# WaveformMorpher.net
KiCad netlist of a schematic drawn in EAGLE
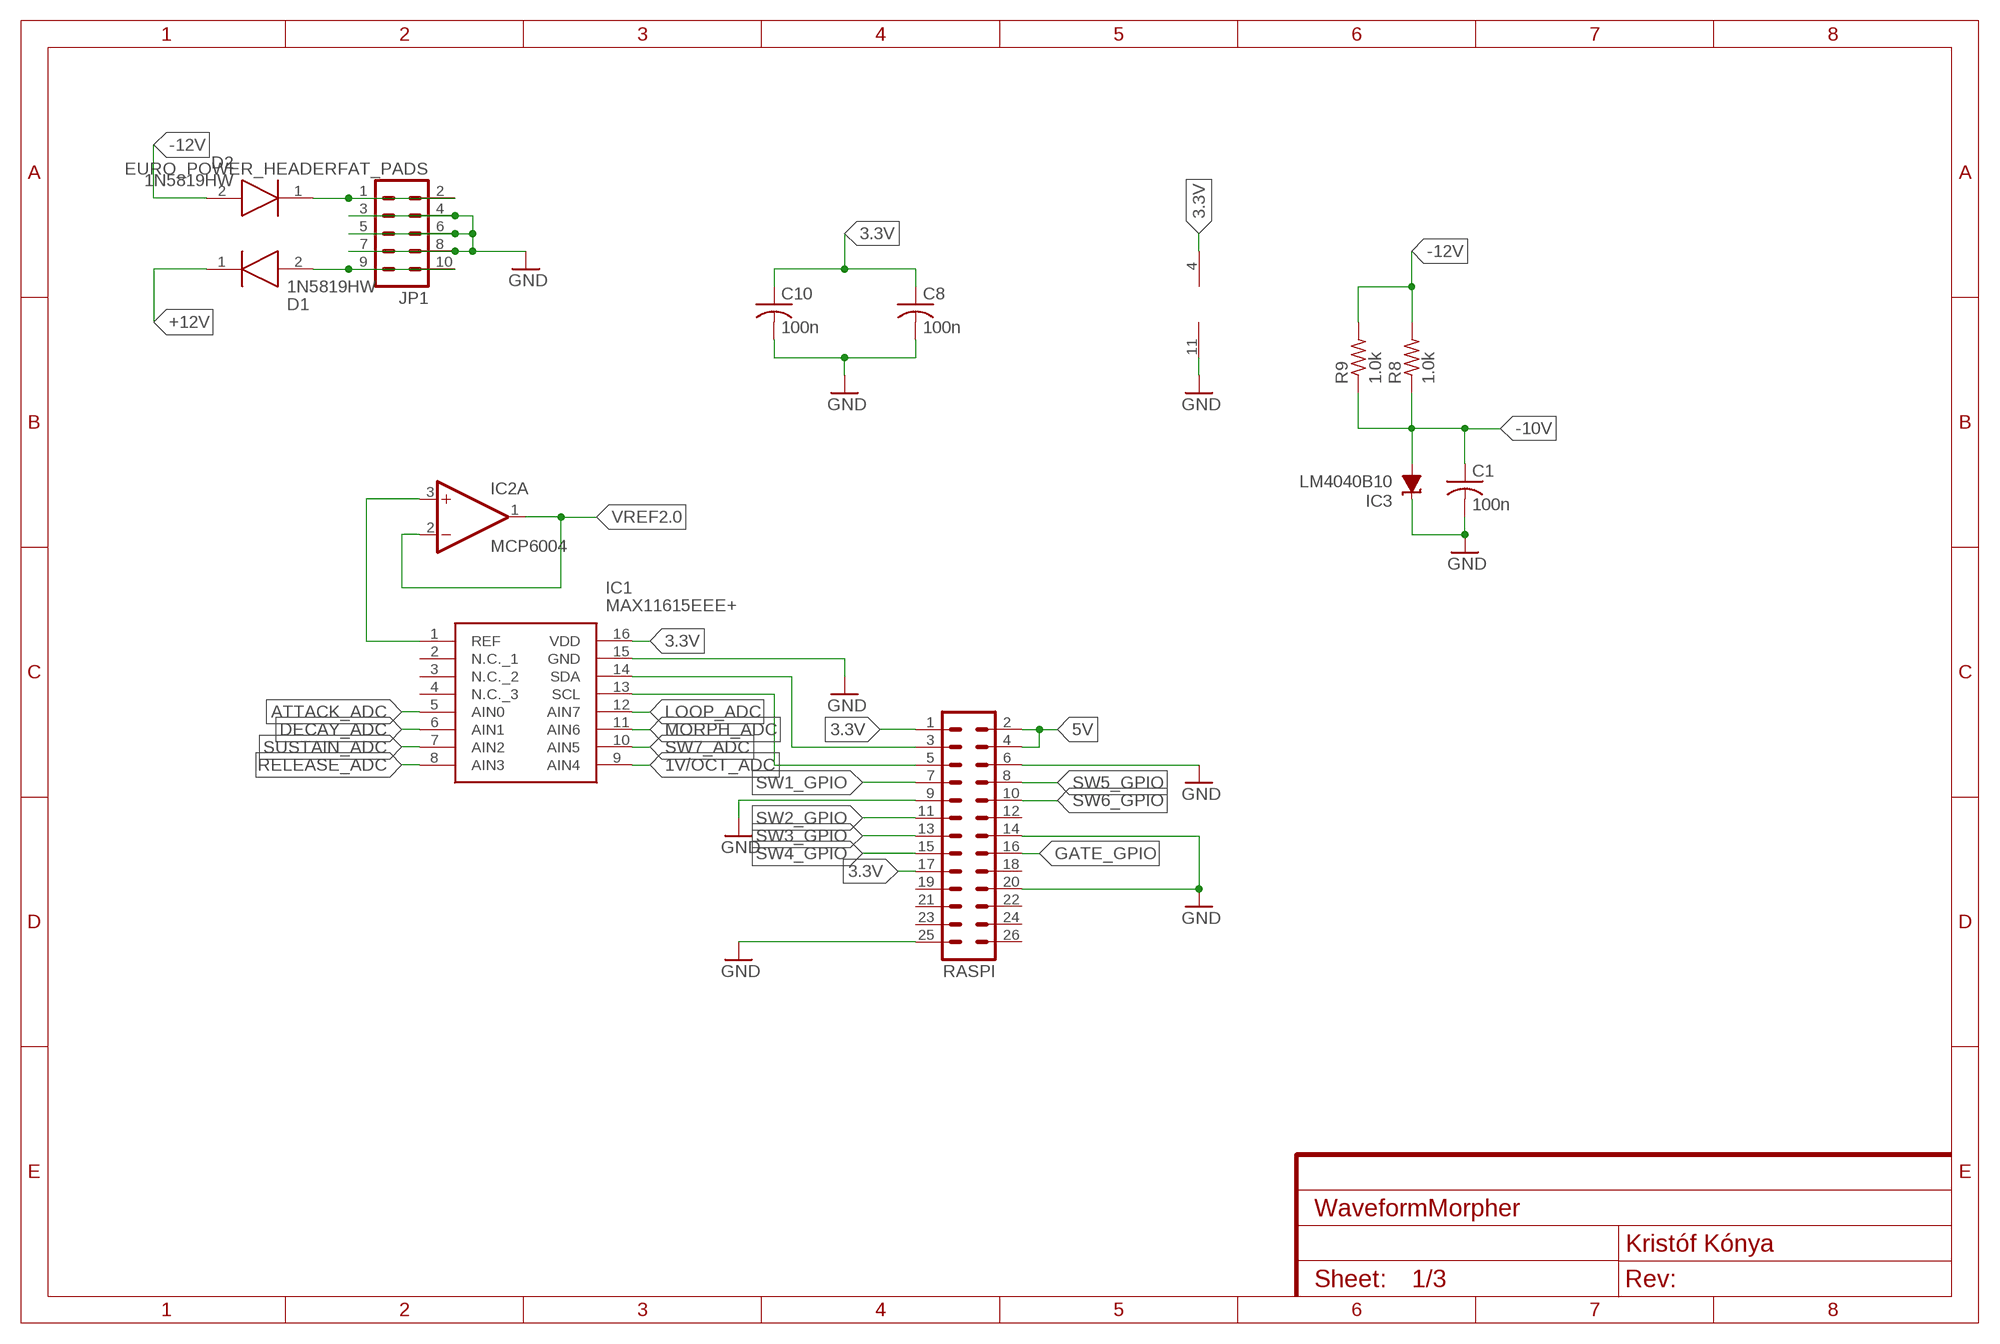
[diagram p0: schematic, sheet 1]
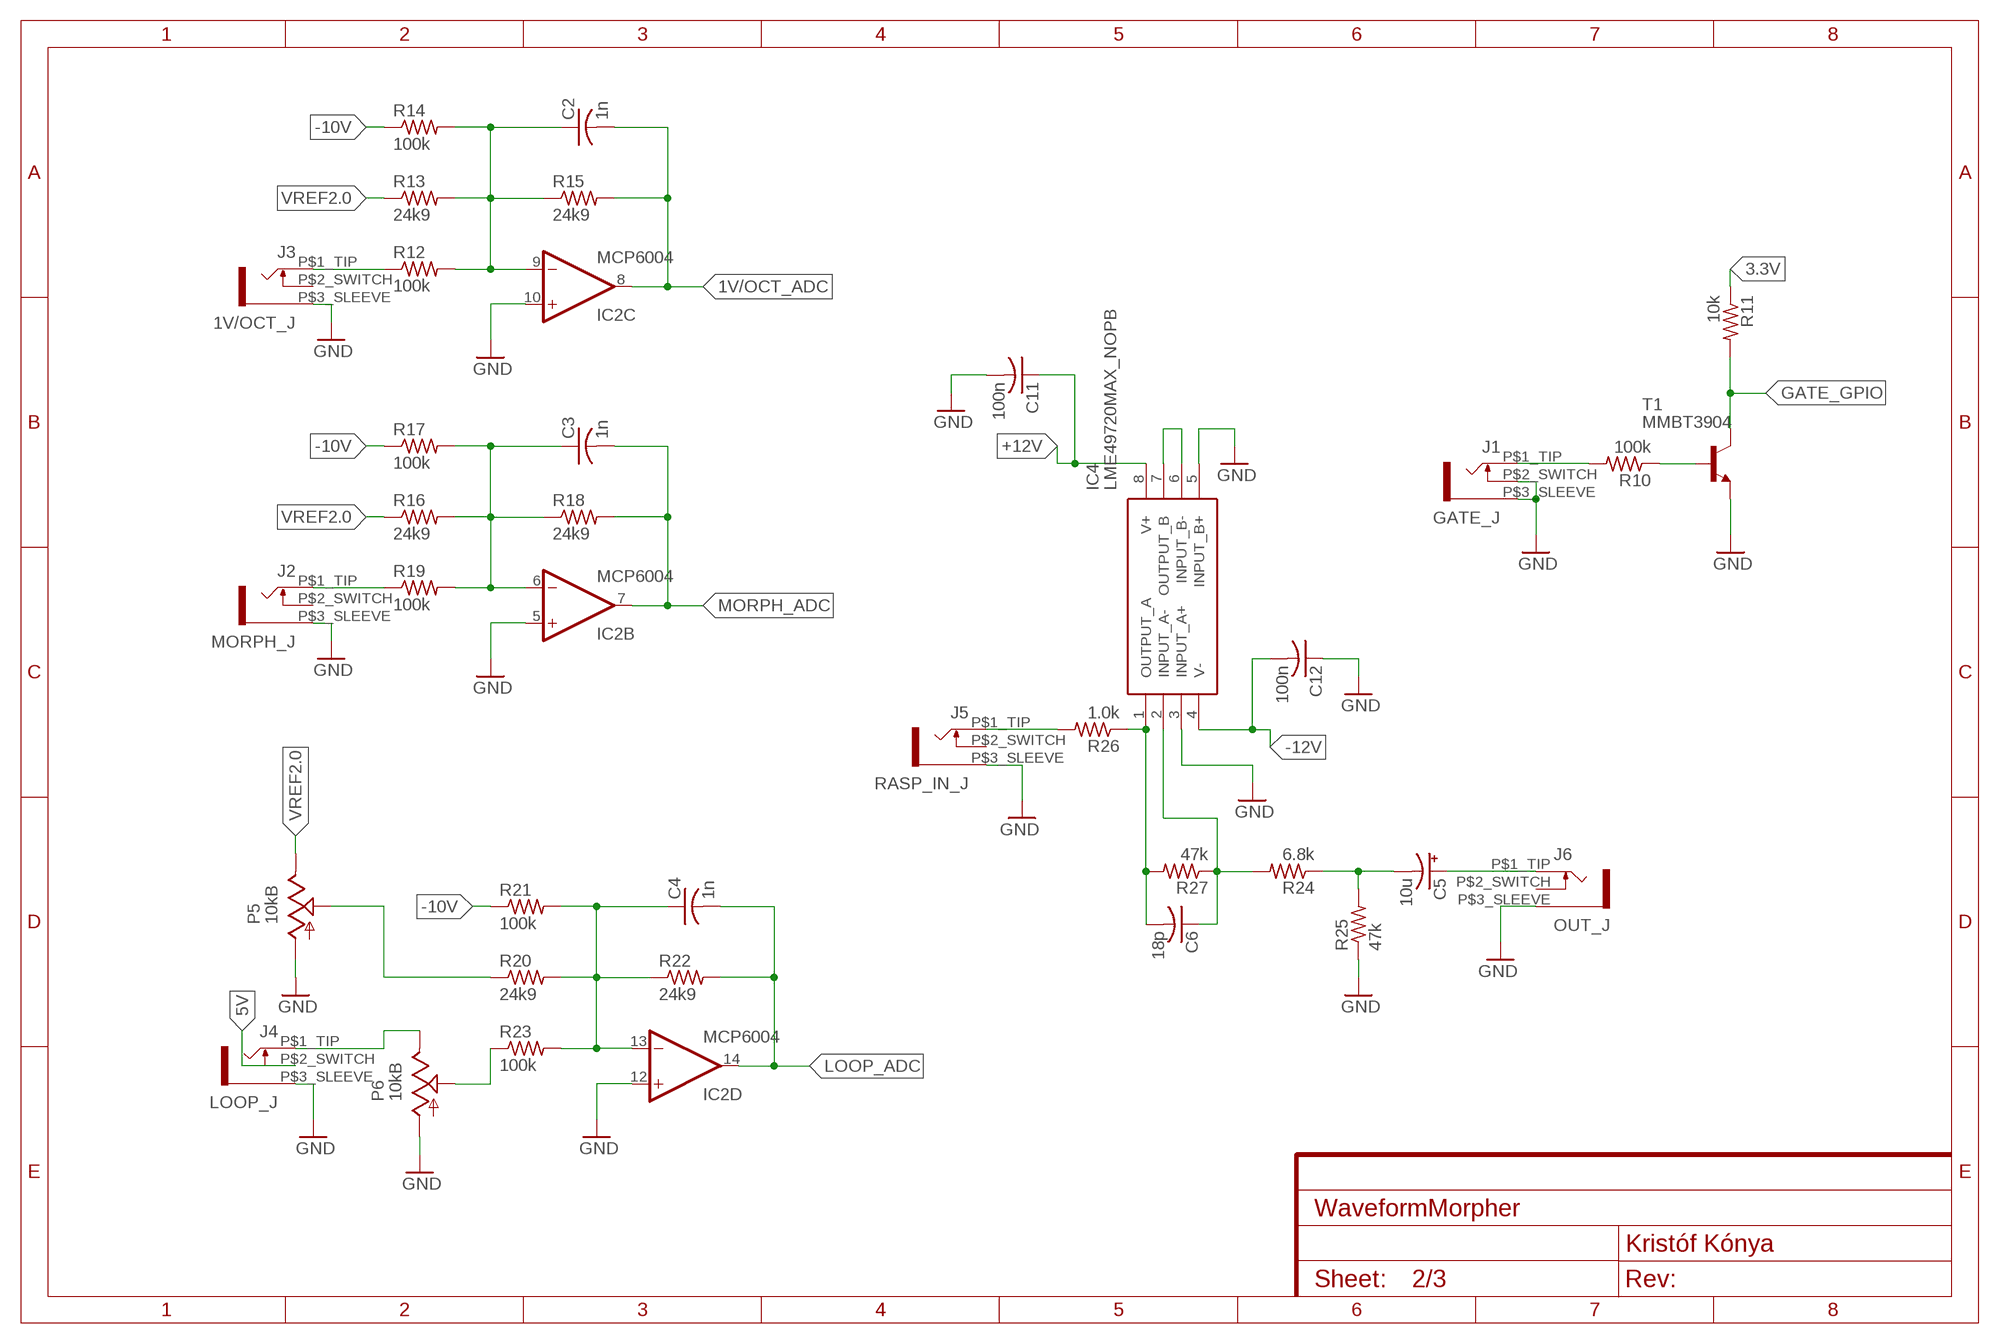
[diagram p1: schematic, sheet 2]
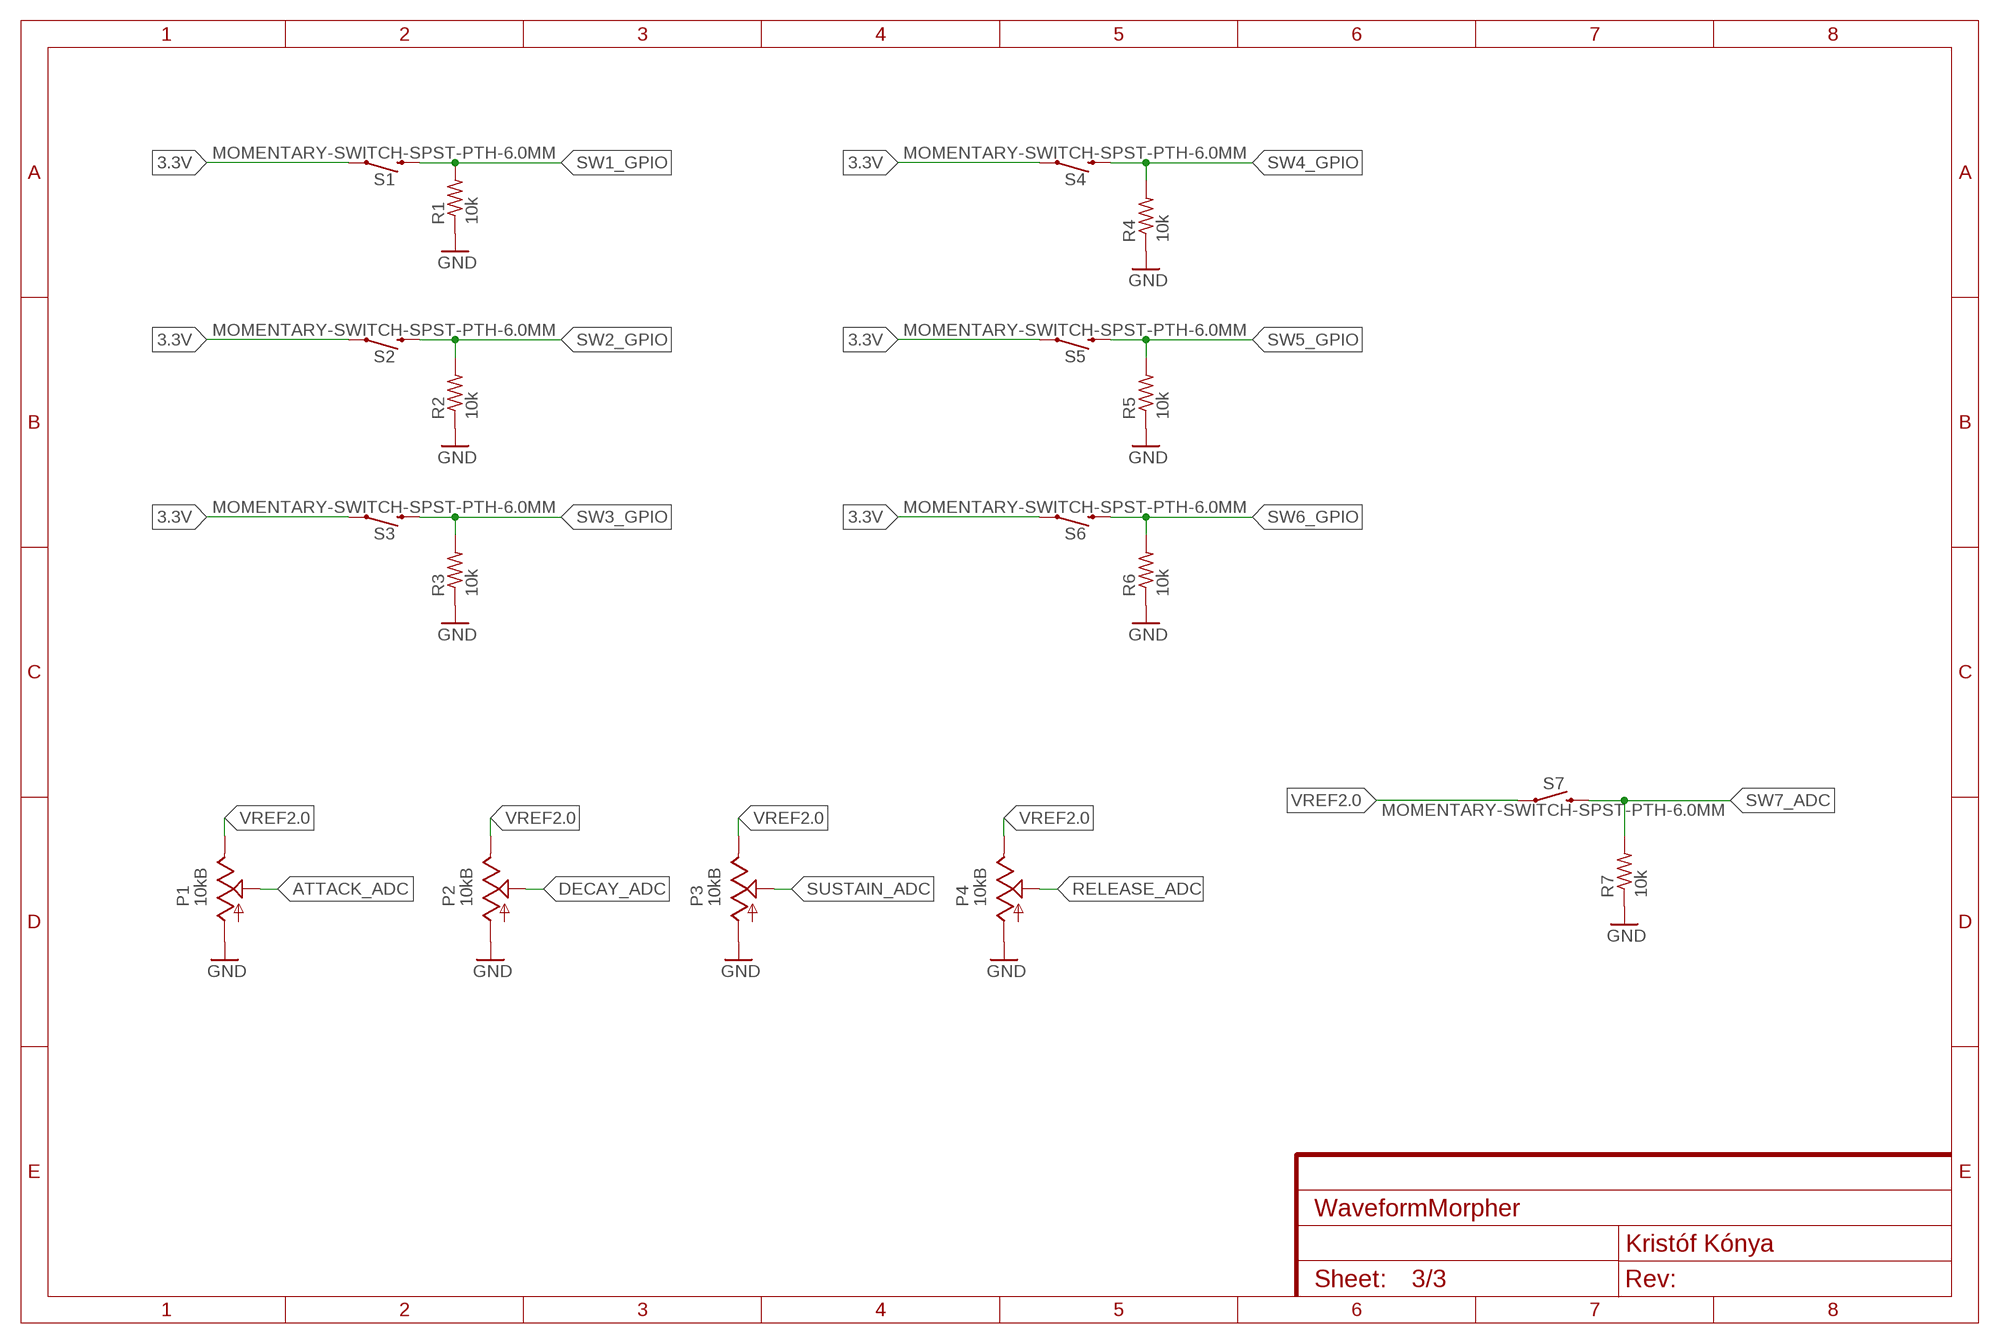
[diagram p2: schematic, sheet 3]

(export (version "E")
  (design (tool "Eeschema 10.0.6"))
  (components
    (comp (ref "C1")
      (value "100n")
      (footprint "eagle-import:C0603")
      (libsource (lib "eagle-import") (part "C-USC0603"))
    )
    (comp (ref "C8")
      (value "100n")
      (footprint "eagle-import:C0603")
      (libsource (lib "eagle-import") (part "C-USC0603"))
    )
    (comp (ref "C10")
      (value "100n")
      (footprint "eagle-import:C0603")
      (libsource (lib "eagle-import") (part "C-USC0603"))
    )
    (comp (ref "D1")
      (value "1N5819HW")
      (footprint "eagle-import:SOD3716X145N")
      (libsource (lib "eagle-import") (part "1N5819HW"))
    )
    (comp (ref "D2")
      (value "1N5819HW")
      (footprint "eagle-import:SOD3716X145N")
      (libsource (lib "eagle-import") (part "1N5819HW"))
    )
    (comp (ref "IC1")
      (value "MAX11615EEE+")
      (footprint "eagle-import:SOP64P602X175-16N")
      (fields (field (name "MOUSER_PART_NUMBER") "700-MAX11615EEE"))
      (libsource (lib "eagle-import") (part "MAX11615EEE+"))
    )
    (comp (ref "IC2")
      (value "MCP6004")
      (footprint "eagle-import:SO14")
      (libsource (lib "eagle-import") (part "TL074D"))
    )
    (comp (ref "IC3")
      (value "LM4040B10")
      (footprint "eagle-import:DBZ_R-PDSO-G3")
      (fields (field (name "MPN") "LM4041B12IDBZR"))
      (libsource (lib "eagle-import") (part "LM4041DBZB12"))
    )
    (comp (ref "JP1")
      (value "EURO_POWER_HEADERFAT_PADS")
      (footprint "eagle-import:EURO_PWR_HEADER_FAT")
      (libsource (lib "eagle-import") (part "EURO_POWER_HEADERFAT_PADS"))
    )
    (comp (ref "R8")
      (value "1.0k")
      (footprint "eagle-import:R0603")
      (libsource (lib "eagle-import") (part "R-US_R0603"))
    )
    (comp (ref "R9")
      (value "1.0k")
      (footprint "eagle-import:R0603")
      (libsource (lib "eagle-import") (part "R-US_R0603"))
    )
    (comp (ref "RASPI")
      (value "MA13-2")
      (footprint "eagle-import:MA13-2")
      (libsource (lib "eagle-import") (part "MA13-2"))
    )
    (comp (ref "C2")
      (value "1n")
      (footprint "eagle-import:C0603")
      (libsource (lib "eagle-import") (part "C-USC0603"))
    )
    (comp (ref "C3")
      (value "1n")
      (footprint "eagle-import:C0603")
      (libsource (lib "eagle-import") (part "C-USC0603"))
    )
    (comp (ref "C4")
      (value "1n")
      (footprint "eagle-import:C0603")
      (libsource (lib "eagle-import") (part "C-USC0603"))
    )
    (comp (ref "C5")
      (value "10u")
      (footprint "eagle-import:PANASONIC_B")
      (libsource (lib "eagle-import") (part "CPOL-USB"))
    )
    (comp (ref "C6")
      (value "18p")
      (footprint "eagle-import:C0603")
      (libsource (lib "eagle-import") (part "C-USC0603"))
    )
    (comp (ref "C11")
      (value "100n")
      (footprint "eagle-import:C0603")
      (libsource (lib "eagle-import") (part "C-USC0603"))
    )
    (comp (ref "C12")
      (value "100n")
      (footprint "eagle-import:C0603")
      (libsource (lib "eagle-import") (part "C-USC0603"))
    )
    (comp (ref "IC4")
      (value "LME49720MAX_NOPB")
      (footprint "eagle-import:SOIC127P600X175-8N")
      (fields
        (field (name "MANUFACTURER_PART_NUMBER") "LME49720MAX/NOPB")
        (field (name "MOUSER_PART_NUMBER") "926-LME49720MAX/NOPB")
      )
      (libsource (lib "eagle-import") (part "LME49720MAX_NOPB"))
    )
    (comp (ref "J1")
      (value "GATE_J")
      (footprint "eagle-import:WQP-PJ301M-12_JACK")
      (libsource (lib "eagle-import") (part "WQP-PJ301M-12_JACK"))
    )
    (comp (ref "J2")
      (value "MORPH_J")
      (footprint "eagle-import:WQP-PJ301M-12_JACK")
      (libsource (lib "eagle-import") (part "WQP-PJ301M-12_JACK"))
    )
    (comp (ref "J3")
      (value "1V/OCT_J")
      (footprint "eagle-import:WQP-PJ301M-12_JACK")
      (libsource (lib "eagle-import") (part "WQP-PJ301M-12_JACK"))
    )
    (comp (ref "J4")
      (value "LOOP_J")
      (footprint "eagle-import:WQP-PJ301M-12_JACK")
      (libsource (lib "eagle-import") (part "WQP-PJ301M-12_JACK"))
    )
    (comp (ref "J5")
      (value "RASP_IN_J")
      (footprint "eagle-import:WQP-PJ301M-12_JACK")
      (libsource (lib "eagle-import") (part "WQP-PJ301M-12_JACK"))
    )
    (comp (ref "J6")
      (value "OUT_J")
      (footprint "eagle-import:WQP-PJ301M-12_JACK")
      (libsource (lib "eagle-import") (part "WQP-PJ301M-12_JACK"))
    )
    (comp (ref "P5")
      (value "10kB")
      (footprint "eagle-import:9MM_SNAP-IN_POT")
      (libsource (lib "eagle-import") (part "9MM_SNAP-IN_POT_"))
    )
    (comp (ref "P6")
      (value "10kB")
      (footprint "eagle-import:9MM_SNAP-IN_POT")
      (libsource (lib "eagle-import") (part "9MM_SNAP-IN_POT_"))
    )
    (comp (ref "R10")
      (value "100k")
      (footprint "eagle-import:R0603")
      (libsource (lib "eagle-import") (part "R-US_R0603"))
    )
    (comp (ref "R11")
      (value "10k")
      (footprint "eagle-import:R0603")
      (libsource (lib "eagle-import") (part "R-US_R0603"))
    )
    (comp (ref "R12")
      (value "100k")
      (footprint "eagle-import:R0603")
      (libsource (lib "eagle-import") (part "R-US_R0603"))
    )
    (comp (ref "R13")
      (value "24k9")
      (footprint "eagle-import:R0603")
      (libsource (lib "eagle-import") (part "R-US_R0603"))
    )
    (comp (ref "R14")
      (value "100k")
      (footprint "eagle-import:R0603")
      (libsource (lib "eagle-import") (part "R-US_R0603"))
    )
    (comp (ref "R15")
      (value "24k9")
      (footprint "eagle-import:R0603")
      (libsource (lib "eagle-import") (part "R-US_R0603"))
    )
    (comp (ref "R16")
      (value "24k9")
      (footprint "eagle-import:R0603")
      (libsource (lib "eagle-import") (part "R-US_R0603"))
    )
    (comp (ref "R17")
      (value "100k")
      (footprint "eagle-import:R0603")
      (libsource (lib "eagle-import") (part "R-US_R0603"))
    )
    (comp (ref "R18")
      (value "24k9")
      (footprint "eagle-import:R0603")
      (libsource (lib "eagle-import") (part "R-US_R0603"))
    )
    (comp (ref "R19")
      (value "100k")
      (footprint "eagle-import:R0603")
      (libsource (lib "eagle-import") (part "R-US_R0603"))
    )
    (comp (ref "R20")
      (value "24k9")
      (footprint "eagle-import:R0603")
      (libsource (lib "eagle-import") (part "R-US_R0603"))
    )
    (comp (ref "R21")
      (value "100k")
      (footprint "eagle-import:R0603")
      (libsource (lib "eagle-import") (part "R-US_R0603"))
    )
    (comp (ref "R22")
      (value "24k9")
      (footprint "eagle-import:R0603")
      (libsource (lib "eagle-import") (part "R-US_R0603"))
    )
    (comp (ref "R23")
      (value "100k")
      (footprint "eagle-import:R0603")
      (libsource (lib "eagle-import") (part "R-US_R0603"))
    )
    (comp (ref "R24")
      (value "6.8k")
      (footprint "eagle-import:R0603")
      (libsource (lib "eagle-import") (part "R-US_R0603"))
    )
    (comp (ref "R25")
      (value "47k")
      (footprint "eagle-import:R0603")
      (libsource (lib "eagle-import") (part "R-US_R0603"))
    )
    (comp (ref "R26")
      (value "1.0k")
      (footprint "eagle-import:R0603")
      (libsource (lib "eagle-import") (part "R-US_R0603"))
    )
    (comp (ref "R27")
      (value "47k")
      (footprint "eagle-import:R0603")
      (libsource (lib "eagle-import") (part "R-US_R0603"))
    )
    (comp (ref "T1")
      (value "MMBT3904")
      (footprint "eagle-import:SOT23-BEC")
      (libsource (lib "eagle-import") (part "-NPN-SOT23-BECMMBT3904LT1"))
    )
    (comp (ref "P1")
      (value "10kB")
      (footprint "eagle-import:9MM_SNAP-IN_POT")
      (libsource (lib "eagle-import") (part "9MM_SNAP-IN_POT_"))
    )
    (comp (ref "P2")
      (value "10kB")
      (footprint "eagle-import:9MM_SNAP-IN_POT")
      (libsource (lib "eagle-import") (part "9MM_SNAP-IN_POT_"))
    )
    (comp (ref "P3")
      (value "10kB")
      (footprint "eagle-import:9MM_SNAP-IN_POT")
      (libsource (lib "eagle-import") (part "9MM_SNAP-IN_POT_"))
    )
    (comp (ref "P4")
      (value "10kB")
      (footprint "eagle-import:9MM_SNAP-IN_POT")
      (libsource (lib "eagle-import") (part "9MM_SNAP-IN_POT_"))
    )
    (comp (ref "R1")
      (value "10k")
      (footprint "eagle-import:R0603")
      (libsource (lib "eagle-import") (part "R-US_R0603"))
    )
    (comp (ref "R2")
      (value "10k")
      (footprint "eagle-import:R0603")
      (libsource (lib "eagle-import") (part "R-US_R0603"))
    )
    (comp (ref "R3")
      (value "10k")
      (footprint "eagle-import:R0603")
      (libsource (lib "eagle-import") (part "R-US_R0603"))
    )
    (comp (ref "R4")
      (value "10k")
      (footprint "eagle-import:R0603")
      (libsource (lib "eagle-import") (part "R-US_R0603"))
    )
    (comp (ref "R5")
      (value "10k")
      (footprint "eagle-import:R0603")
      (libsource (lib "eagle-import") (part "R-US_R0603"))
    )
    (comp (ref "R6")
      (value "10k")
      (footprint "eagle-import:R0603")
      (libsource (lib "eagle-import") (part "R-US_R0603"))
    )
    (comp (ref "R7")
      (value "10k")
      (footprint "eagle-import:R0603")
      (libsource (lib "eagle-import") (part "R-US_R0603"))
    )
    (comp (ref "S1")
      (value "MOMENTARY-SWITCH-SPST-PTH-6.0MM")
      (footprint "eagle-import:TACTILE_SWITCH_PTH_6.0MM")
      (libsource (lib "eagle-import") (part "MOMENTARY-SWITCH-SPST-PTH-6.0MM"))
    )
    (comp (ref "S2")
      (value "MOMENTARY-SWITCH-SPST-PTH-6.0MM")
      (footprint "eagle-import:TACTILE_SWITCH_PTH_6.0MM")
      (libsource (lib "eagle-import") (part "MOMENTARY-SWITCH-SPST-PTH-6.0MM"))
    )
    (comp (ref "S3")
      (value "MOMENTARY-SWITCH-SPST-PTH-6.0MM")
      (footprint "eagle-import:TACTILE_SWITCH_PTH_6.0MM")
      (libsource (lib "eagle-import") (part "MOMENTARY-SWITCH-SPST-PTH-6.0MM"))
    )
    (comp (ref "S4")
      (value "MOMENTARY-SWITCH-SPST-PTH-6.0MM")
      (footprint "eagle-import:TACTILE_SWITCH_PTH_6.0MM")
      (libsource (lib "eagle-import") (part "MOMENTARY-SWITCH-SPST-PTH-6.0MM"))
    )
    (comp (ref "S5")
      (value "MOMENTARY-SWITCH-SPST-PTH-6.0MM")
      (footprint "eagle-import:TACTILE_SWITCH_PTH_6.0MM")
      (libsource (lib "eagle-import") (part "MOMENTARY-SWITCH-SPST-PTH-6.0MM"))
    )
    (comp (ref "S6")
      (value "MOMENTARY-SWITCH-SPST-PTH-6.0MM")
      (footprint "eagle-import:TACTILE_SWITCH_PTH_6.0MM")
      (libsource (lib "eagle-import") (part "MOMENTARY-SWITCH-SPST-PTH-6.0MM"))
    )
    (comp (ref "S7")
      (value "MOMENTARY-SWITCH-SPST-PTH-6.0MM")
      (footprint "eagle-import:TACTILE_SWITCH_PTH_6.0MM")
      (libsource (lib "eagle-import") (part "MOMENTARY-SWITCH-SPST-PTH-6.0MM"))
    )
  )
  (nets
    (net (code "1") (name "+12V") (class "Default")
      (node (ref "C11") (pin "1") (pinfunction "1_1") (pintype "passive"))
      (node (ref "D1") (pin "1") (pinfunction "K_1") (pintype "bidirectional"))
      (node (ref "IC4") (pin "8") (pinfunction "V+_8") (pintype "power_in"))
    )
    (net (code "2") (name "-10V") (class "Default")
      (node (ref "C1") (pin "1") (pinfunction "1_1") (pintype "passive"))
      (node (ref "IC3") (pin "2") (pinfunction "A_2") (pintype "passive"))
      (node (ref "R14") (pin "1") (pinfunction "1_1") (pintype "passive"))
      (node (ref "R17") (pin "1") (pinfunction "1_1") (pintype "passive"))
      (node (ref "R21") (pin "1") (pinfunction "1_1") (pintype "passive"))
      (node (ref "R8") (pin "1") (pinfunction "1_1") (pintype "passive"))
      (node (ref "R9") (pin "1") (pinfunction "1_1") (pintype "passive"))
    )
    (net (code "3") (name "-12V") (class "Default")
      (node (ref "C12") (pin "2") (pinfunction "2_2") (pintype "passive"))
      (node (ref "D2") (pin "2") (pinfunction "A_2") (pintype "bidirectional"))
      (node (ref "IC4") (pin "4") (pinfunction "V-_4") (pintype "power_in"))
      (node (ref "R8") (pin "2") (pinfunction "2_2") (pintype "passive"))
      (node (ref "R9") (pin "2") (pinfunction "2_2") (pintype "passive"))
    )
    (net (code "4") (name "1V{slash}OCT_ADC") (class "Default")
      (node (ref "C2") (pin "2") (pinfunction "2_2") (pintype "passive"))
      (node (ref "IC1") (pin "9") (pinfunction "AIN4_9") (pintype "input"))
      (node (ref "IC2") (pin "8") (pinfunction "OUT_8") (pintype "output"))
      (node (ref "R15") (pin "2") (pinfunction "2_2") (pintype "passive"))
    )
    (net (code "5") (name "3.3V") (class "Default")
      (node (ref "C10") (pin "1") (pinfunction "1_1") (pintype "passive"))
      (node (ref "C8") (pin "1") (pinfunction "1_1") (pintype "passive"))
      (node (ref "IC1") (pin "16") (pinfunction "VDD_16") (pintype "power_in"))
      (node (ref "IC2") (pin "4") (pinfunction "V+_4") (pintype "power_in"))
      (node (ref "R11") (pin "1") (pinfunction "1_1") (pintype "passive"))
      (node (ref "RASPI") (pin "1") (pinfunction "1_1") (pintype "passive"))
      (node (ref "RASPI") (pin "17") (pinfunction "17_17") (pintype "passive"))
      (node (ref "S1") (pin "1") (pinfunction "1_1") (pintype "passive"))
      (node (ref "S2") (pin "1") (pinfunction "1_1") (pintype "passive"))
      (node (ref "S3") (pin "1") (pinfunction "1_1") (pintype "passive"))
      (node (ref "S4") (pin "1") (pinfunction "1_1") (pintype "passive"))
      (node (ref "S5") (pin "1") (pinfunction "1_1") (pintype "passive"))
      (node (ref "S6") (pin "1") (pinfunction "1_1") (pintype "passive"))
    )
    (net (code "6") (name "5V") (class "Default")
      (node (ref "J4") (pin "P$2_SWITCH") (pinfunction "3_P$2_SWITCH") (pintype "passive"))
      (node (ref "RASPI") (pin "2") (pinfunction "2_2") (pintype "passive"))
      (node (ref "RASPI") (pin "4") (pinfunction "4_4") (pintype "passive"))
    )
    (net (code "7") (name "ATTACK_ADC") (class "Default")
      (node (ref "IC1") (pin "5") (pinfunction "AIN0_5") (pintype "input"))
      (node (ref "P1") (pin "2") (pinfunction "S_2") (pintype "passive"))
    )
    (net (code "8") (name "DECAY_ADC") (class "Default")
      (node (ref "IC1") (pin "6") (pinfunction "AIN1_6") (pintype "input"))
      (node (ref "P2") (pin "2") (pinfunction "S_2") (pintype "passive"))
    )
    (net (code "9") (name "GATE_GPIO") (class "Default")
      (node (ref "R11") (pin "2") (pinfunction "2_2") (pintype "passive"))
      (node (ref "RASPI") (pin "16") (pinfunction "16_16") (pintype "passive"))
      (node (ref "T1") (pin "C") (pinfunction "C_C") (pintype "passive"))
    )
    (net (code "10") (name "GND") (class "Default")
      (node (ref "C1") (pin "2") (pinfunction "2_2") (pintype "passive"))
      (node (ref "C10") (pin "2") (pinfunction "2_2") (pintype "passive"))
      (node (ref "C11") (pin "2") (pinfunction "2_2") (pintype "passive"))
      (node (ref "C12") (pin "1") (pinfunction "1_1") (pintype "passive"))
      (node (ref "C8") (pin "2") (pinfunction "2_2") (pintype "passive"))
      (node (ref "IC1") (pin "15") (pinfunction "GND_15") (pintype "power_in"))
      (node (ref "IC2") (pin "10") (pinfunction "+IN_10") (pintype "input"))
      (node (ref "IC2") (pin "11") (pinfunction "V-_11") (pintype "power_in"))
      (node (ref "IC2") (pin "12") (pinfunction "+IN_12") (pintype "input"))
      (node (ref "IC2") (pin "5") (pinfunction "+IN_5") (pintype "input"))
      (node (ref "IC3") (pin "1") (pinfunction "C_1") (pintype "passive"))
      (node (ref "IC4") (pin "3") (pinfunction "INPUT_A+_3") (pintype "input"))
      (node (ref "IC4") (pin "5") (pinfunction "INPUT_B+_5") (pintype "input"))
      (node (ref "J1") (pin "P$2_SWITCH") (pinfunction "3_P$2_SWITCH") (pintype "passive"))
      (node (ref "J1") (pin "P$3_SLEEVE") (pinfunction "1_P$3_SLEEVE") (pintype "passive"))
      (node (ref "J2") (pin "P$3_SLEEVE") (pinfunction "1_P$3_SLEEVE") (pintype "passive"))
      (node (ref "J3") (pin "P$3_SLEEVE") (pinfunction "1_P$3_SLEEVE") (pintype "passive"))
      (node (ref "J4") (pin "P$3_SLEEVE") (pinfunction "1_P$3_SLEEVE") (pintype "passive"))
      (node (ref "J5") (pin "P$3_SLEEVE") (pinfunction "1_P$3_SLEEVE") (pintype "passive"))
      (node (ref "J6") (pin "P$3_SLEEVE") (pinfunction "1_P$3_SLEEVE") (pintype "passive"))
      (node (ref "JP1") (pin "3") (pinfunction "3_3") (pintype "passive"))
      (node (ref "JP1") (pin "4") (pinfunction "4_4") (pintype "passive"))
      (node (ref "JP1") (pin "5") (pinfunction "5_5") (pintype "passive"))
      (node (ref "JP1") (pin "6") (pinfunction "6_6") (pintype "passive"))
      (node (ref "JP1") (pin "7") (pinfunction "7_7") (pintype "passive"))
      (node (ref "JP1") (pin "8") (pinfunction "8_8") (pintype "passive"))
      (node (ref "P1") (pin "1") (pinfunction "A_1") (pintype "passive"))
      (node (ref "P2") (pin "1") (pinfunction "A_1") (pintype "passive"))
      (node (ref "P3") (pin "1") (pinfunction "A_1") (pintype "passive"))
      (node (ref "P4") (pin "1") (pinfunction "A_1") (pintype "passive"))
      (node (ref "P5") (pin "1") (pinfunction "A_1") (pintype "passive"))
      (node (ref "P6") (pin "1") (pinfunction "A_1") (pintype "passive"))
      (node (ref "R1") (pin "1") (pinfunction "1_1") (pintype "passive"))
      (node (ref "R2") (pin "1") (pinfunction "1_1") (pintype "passive"))
      (node (ref "R25") (pin "1") (pinfunction "1_1") (pintype "passive"))
      (node (ref "R3") (pin "1") (pinfunction "1_1") (pintype "passive"))
      (node (ref "R4") (pin "1") (pinfunction "1_1") (pintype "passive"))
      (node (ref "R5") (pin "1") (pinfunction "1_1") (pintype "passive"))
      (node (ref "R6") (pin "1") (pinfunction "1_1") (pintype "passive"))
      (node (ref "R7") (pin "1") (pinfunction "1_1") (pintype "passive"))
      (node (ref "RASPI") (pin "14") (pinfunction "14_14") (pintype "passive"))
      (node (ref "RASPI") (pin "20") (pinfunction "20_20") (pintype "passive"))
      (node (ref "RASPI") (pin "25") (pinfunction "25_25") (pintype "passive"))
      (node (ref "RASPI") (pin "6") (pinfunction "6_6") (pintype "passive"))
      (node (ref "RASPI") (pin "9") (pinfunction "9_9") (pintype "passive"))
      (node (ref "T1") (pin "E") (pinfunction "E_E") (pintype "passive"))
    )
    (net (code "11") (name "LOOP_ADC") (class "Default")
      (node (ref "C4") (pin "2") (pinfunction "2_2") (pintype "passive"))
      (node (ref "IC1") (pin "12") (pinfunction "AIN7_12") (pintype "input"))
      (node (ref "IC2") (pin "14") (pinfunction "OUT_14") (pintype "output"))
      (node (ref "R22") (pin "2") (pinfunction "2_2") (pintype "passive"))
    )
    (net (code "12") (name "MORPH_ADC") (class "Default")
      (node (ref "C3") (pin "2") (pinfunction "2_2") (pintype "passive"))
      (node (ref "IC1") (pin "11") (pinfunction "AIN6_11") (pintype "input"))
      (node (ref "IC2") (pin "7") (pinfunction "OUT_7") (pintype "output"))
      (node (ref "R18") (pin "2") (pinfunction "2_2") (pintype "passive"))
    )
    (net (code "13") (name "Net-(C5-Pad-)") (class "Default")
      (node (ref "C5") (pin "-") (pinfunction "-_-") (pintype "passive"))
      (node (ref "R24") (pin "1") (pinfunction "1_1") (pintype "passive"))
      (node (ref "R25") (pin "2") (pinfunction "2_2") (pintype "passive"))
    )
    (net (code "14") (name "Net-(D1-A)") (class "Default")
      (node (ref "D1") (pin "2") (pinfunction "A_2") (pintype "bidirectional"))
      (node (ref "JP1") (pin "10") (pinfunction "10_10") (pintype "passive"))
      (node (ref "JP1") (pin "9") (pinfunction "9_9") (pintype "passive"))
    )
    (net (code "15") (name "Net-(D2-K)") (class "Default")
      (node (ref "D2") (pin "1") (pinfunction "K_1") (pintype "bidirectional"))
      (node (ref "JP1") (pin "1") (pinfunction "1_1") (pintype "passive"))
      (node (ref "JP1") (pin "2") (pinfunction "2_2") (pintype "passive"))
    )
    (net (code "16") (name "Net-(IC1-REF)") (class "Default")
      (node (ref "IC1") (pin "1") (pinfunction "REF_1") (pintype "input"))
      (node (ref "IC2") (pin "3") (pinfunction "+IN_3") (pintype "input"))
    )
    (net (code "17") (name "Net-(IC1-SCL)") (class "Default")
      (node (ref "IC1") (pin "13") (pinfunction "SCL_13") (pintype "bidirectional"))
      (node (ref "RASPI") (pin "5") (pinfunction "5_5") (pintype "passive"))
    )
    (net (code "18") (name "Net-(IC1-SDA)") (class "Default")
      (node (ref "IC1") (pin "14") (pinfunction "SDA_14") (pintype "bidirectional"))
      (node (ref "RASPI") (pin "3") (pinfunction "3_3") (pintype "passive"))
    )
    (net (code "19") (name "Net-(IC2B--IN)") (class "Default")
      (node (ref "C3") (pin "1") (pinfunction "1_1") (pintype "passive"))
      (node (ref "IC2") (pin "6") (pinfunction "-IN_6") (pintype "input"))
      (node (ref "R16") (pin "2") (pinfunction "2_2") (pintype "passive"))
      (node (ref "R17") (pin "2") (pinfunction "2_2") (pintype "passive"))
      (node (ref "R18") (pin "1") (pinfunction "1_1") (pintype "passive"))
      (node (ref "R19") (pin "2") (pinfunction "2_2") (pintype "passive"))
    )
    (net (code "20") (name "Net-(IC2C--IN)") (class "Default")
      (node (ref "C2") (pin "1") (pinfunction "1_1") (pintype "passive"))
      (node (ref "IC2") (pin "9") (pinfunction "-IN_9") (pintype "input"))
      (node (ref "R12") (pin "2") (pinfunction "2_2") (pintype "passive"))
      (node (ref "R13") (pin "2") (pinfunction "2_2") (pintype "passive"))
      (node (ref "R14") (pin "2") (pinfunction "2_2") (pintype "passive"))
      (node (ref "R15") (pin "1") (pinfunction "1_1") (pintype "passive"))
    )
    (net (code "21") (name "Net-(IC2D--IN)") (class "Default")
      (node (ref "C4") (pin "1") (pinfunction "1_1") (pintype "passive"))
      (node (ref "IC2") (pin "13") (pinfunction "-IN_13") (pintype "input"))
      (node (ref "R20") (pin "2") (pinfunction "2_2") (pintype "passive"))
      (node (ref "R21") (pin "2") (pinfunction "2_2") (pintype "passive"))
      (node (ref "R22") (pin "1") (pinfunction "1_1") (pintype "passive"))
      (node (ref "R23") (pin "2") (pinfunction "2_2") (pintype "passive"))
    )
    (net (code "22") (name "Net-(IC4-INPUT_A-)") (class "Default")
      (node (ref "C6") (pin "1") (pinfunction "1_1") (pintype "passive"))
      (node (ref "IC4") (pin "2") (pinfunction "INPUT_A-_2") (pintype "input"))
      (node (ref "R24") (pin "2") (pinfunction "2_2") (pintype "passive"))
      (node (ref "R27") (pin "1") (pinfunction "1_1") (pintype "passive"))
    )
    (net (code "23") (name "Net-(IC4-INPUT_B-)") (class "Default")
      (node (ref "IC4") (pin "6") (pinfunction "INPUT_B-_6") (pintype "input"))
      (node (ref "IC4") (pin "7") (pinfunction "OUTPUT_B_7") (pintype "output"))
    )
    (net (code "24") (name "Net-(IC4-OUTPUT_A)") (class "Default")
      (node (ref "C6") (pin "2") (pinfunction "2_2") (pintype "passive"))
      (node (ref "IC4") (pin "1") (pinfunction "OUTPUT_A_1") (pintype "output"))
      (node (ref "R26") (pin "1") (pinfunction "1_1") (pintype "passive"))
      (node (ref "R27") (pin "2") (pinfunction "2_2") (pintype "passive"))
    )
    (net (code "25") (name "Net-(J1-2)") (class "Default")
      (node (ref "J1") (pin "P$1_TIP") (pinfunction "2_P$1_TIP") (pintype "passive"))
      (node (ref "R10") (pin "2") (pinfunction "2_2") (pintype "passive"))
    )
    (net (code "26") (name "Net-(J2-2)") (class "Default")
      (node (ref "J2") (pin "P$1_TIP") (pinfunction "2_P$1_TIP") (pintype "passive"))
      (node (ref "R19") (pin "1") (pinfunction "1_1") (pintype "passive"))
    )
    (net (code "27") (name "Net-(J3-2)") (class "Default")
      (node (ref "J3") (pin "P$1_TIP") (pinfunction "2_P$1_TIP") (pintype "passive"))
      (node (ref "R12") (pin "1") (pinfunction "1_1") (pintype "passive"))
    )
    (net (code "28") (name "Net-(J4-2)") (class "Default")
      (node (ref "J4") (pin "P$1_TIP") (pinfunction "2_P$1_TIP") (pintype "passive"))
      (node (ref "P6") (pin "3") (pinfunction "E_3") (pintype "passive"))
    )
    (net (code "29") (name "Net-(J5-2)") (class "Default")
      (node (ref "J5") (pin "P$1_TIP") (pinfunction "2_P$1_TIP") (pintype "passive"))
      (node (ref "R26") (pin "2") (pinfunction "2_2") (pintype "passive"))
    )
    (net (code "30") (name "Net-(J6-2)") (class "Default")
      (node (ref "C5") (pin "+") (pinfunction "+_+") (pintype "passive"))
      (node (ref "J6") (pin "P$1_TIP") (pinfunction "2_P$1_TIP") (pintype "passive"))
    )
    (net (code "31") (name "Net-(P5-S)") (class "Default")
      (node (ref "P5") (pin "2") (pinfunction "S_2") (pintype "passive"))
      (node (ref "R20") (pin "1") (pinfunction "1_1") (pintype "passive"))
    )
    (net (code "32") (name "Net-(P6-S)") (class "Default")
      (node (ref "P6") (pin "2") (pinfunction "S_2") (pintype "passive"))
      (node (ref "R23") (pin "1") (pinfunction "1_1") (pintype "passive"))
    )
    (net (code "33") (name "Net-(R10-Pad1)") (class "Default")
      (node (ref "R10") (pin "1") (pinfunction "1_1") (pintype "passive"))
      (node (ref "T1") (pin "B") (pinfunction "B_B") (pintype "passive"))
    )
    (net (code "34") (name "RELEASE_ADC") (class "Default")
      (node (ref "IC1") (pin "8") (pinfunction "AIN3_8") (pintype "input"))
      (node (ref "P4") (pin "2") (pinfunction "S_2") (pintype "passive"))
    )
    (net (code "35") (name "SUSTAIN_ADC") (class "Default")
      (node (ref "IC1") (pin "7") (pinfunction "AIN2_7") (pintype "input"))
      (node (ref "P3") (pin "2") (pinfunction "S_2") (pintype "passive"))
    )
    (net (code "36") (name "SW1_GPIO") (class "Default")
      (node (ref "R1") (pin "2") (pinfunction "2_2") (pintype "passive"))
      (node (ref "RASPI") (pin "7") (pinfunction "7_7") (pintype "passive"))
      (node (ref "S1") (pin "3") (pinfunction "2_3") (pintype "passive"))
    )
    (net (code "37") (name "SW2_GPIO") (class "Default")
      (node (ref "R2") (pin "2") (pinfunction "2_2") (pintype "passive"))
      (node (ref "RASPI") (pin "11") (pinfunction "11_11") (pintype "passive"))
      (node (ref "S2") (pin "3") (pinfunction "2_3") (pintype "passive"))
    )
    (net (code "38") (name "SW3_GPIO") (class "Default")
      (node (ref "R3") (pin "2") (pinfunction "2_2") (pintype "passive"))
      (node (ref "RASPI") (pin "13") (pinfunction "13_13") (pintype "passive"))
      (node (ref "S3") (pin "3") (pinfunction "2_3") (pintype "passive"))
    )
    (net (code "39") (name "SW4_GPIO") (class "Default")
      (node (ref "R4") (pin "2") (pinfunction "2_2") (pintype "passive"))
      (node (ref "RASPI") (pin "15") (pinfunction "15_15") (pintype "passive"))
      (node (ref "S4") (pin "3") (pinfunction "2_3") (pintype "passive"))
    )
    (net (code "40") (name "SW5_GPIO") (class "Default")
      (node (ref "R5") (pin "2") (pinfunction "2_2") (pintype "passive"))
      (node (ref "RASPI") (pin "8") (pinfunction "8_8") (pintype "passive"))
      (node (ref "S5") (pin "3") (pinfunction "2_3") (pintype "passive"))
    )
    (net (code "41") (name "SW6_GPIO") (class "Default")
      (node (ref "R6") (pin "2") (pinfunction "2_2") (pintype "passive"))
      (node (ref "RASPI") (pin "10") (pinfunction "10_10") (pintype "passive"))
      (node (ref "S6") (pin "3") (pinfunction "2_3") (pintype "passive"))
    )
    (net (code "42") (name "SW7_ADC") (class "Default")
      (node (ref "IC1") (pin "10") (pinfunction "AIN5_10") (pintype "input"))
      (node (ref "R7") (pin "2") (pinfunction "2_2") (pintype "passive"))
      (node (ref "S7") (pin "3") (pinfunction "2_3") (pintype "passive"))
    )
    (net (code "43") (name "VREF2.0") (class "Default")
      (node (ref "IC2") (pin "1") (pinfunction "OUT_1") (pintype "output"))
      (node (ref "IC2") (pin "2") (pinfunction "-IN_2") (pintype "input"))
      (node (ref "P1") (pin "3") (pinfunction "E_3") (pintype "passive"))
      (node (ref "P2") (pin "3") (pinfunction "E_3") (pintype "passive"))
      (node (ref "P3") (pin "3") (pinfunction "E_3") (pintype "passive"))
      (node (ref "P4") (pin "3") (pinfunction "E_3") (pintype "passive"))
      (node (ref "P5") (pin "3") (pinfunction "E_3") (pintype "passive"))
      (node (ref "R13") (pin "1") (pinfunction "1_1") (pintype "passive"))
      (node (ref "R16") (pin "1") (pinfunction "1_1") (pintype "passive"))
      (node (ref "S7") (pin "1") (pinfunction "1_1") (pintype "passive"))
    )
    (net (code "44") (name "unconnected-(IC1-N.C._1-Pad2)") (class "Default")
      (node (ref "IC1") (pin "2") (pinfunction "N.C._1_2") (pintype "bidirectional"))
    )
    (net (code "45") (name "unconnected-(IC1-N.C._2-Pad3)") (class "Default")
      (node (ref "IC1") (pin "3") (pinfunction "N.C._2_3") (pintype "bidirectional"))
    )
    (net (code "46") (name "unconnected-(IC1-N.C._3-Pad4)") (class "Default")
      (node (ref "IC1") (pin "4") (pinfunction "N.C._3_4") (pintype "bidirectional"))
    )
    (net (code "47") (name "unconnected-(J2-3-PadP$2_SWITCH)") (class "Default")
      (node (ref "J2") (pin "P$2_SWITCH") (pinfunction "3_P$2_SWITCH") (pintype "passive"))
    )
    (net (code "48") (name "unconnected-(J3-3-PadP$2_SWITCH)") (class "Default")
      (node (ref "J3") (pin "P$2_SWITCH") (pinfunction "3_P$2_SWITCH") (pintype "passive"))
    )
    (net (code "49") (name "unconnected-(J5-3-PadP$2_SWITCH)") (class "Default")
      (node (ref "J5") (pin "P$2_SWITCH") (pinfunction "3_P$2_SWITCH") (pintype "passive"))
    )
    (net (code "50") (name "unconnected-(J6-3-PadP$2_SWITCH)") (class "Default")
      (node (ref "J6") (pin "P$2_SWITCH") (pinfunction "3_P$2_SWITCH") (pintype "passive"))
    )
    (net (code "51") (name "unconnected-(RASPI-Pad12)") (class "Default")
      (node (ref "RASPI") (pin "12") (pinfunction "12_12") (pintype "passive"))
    )
    (net (code "52") (name "unconnected-(RASPI-Pad18)") (class "Default")
      (node (ref "RASPI") (pin "18") (pinfunction "18_18") (pintype "passive"))
    )
    (net (code "53") (name "unconnected-(RASPI-Pad19)") (class "Default")
      (node (ref "RASPI") (pin "19") (pinfunction "19_19") (pintype "passive"))
    )
    (net (code "54") (name "unconnected-(RASPI-Pad21)") (class "Default")
      (node (ref "RASPI") (pin "21") (pinfunction "21_21") (pintype "passive"))
    )
    (net (code "55") (name "unconnected-(RASPI-Pad22)") (class "Default")
      (node (ref "RASPI") (pin "22") (pinfunction "22_22") (pintype "passive"))
    )
    (net (code "56") (name "unconnected-(RASPI-Pad23)") (class "Default")
      (node (ref "RASPI") (pin "23") (pinfunction "23_23") (pintype "passive"))
    )
    (net (code "57") (name "unconnected-(RASPI-Pad24)") (class "Default")
      (node (ref "RASPI") (pin "24") (pinfunction "24_24") (pintype "passive"))
    )
    (net (code "58") (name "unconnected-(RASPI-Pad26)") (class "Default")
      (node (ref "RASPI") (pin "26") (pinfunction "26_26") (pintype "passive"))
    )
  )
)
